# motor_control.net
KiCad netlist of a schematic drawn in EAGLE
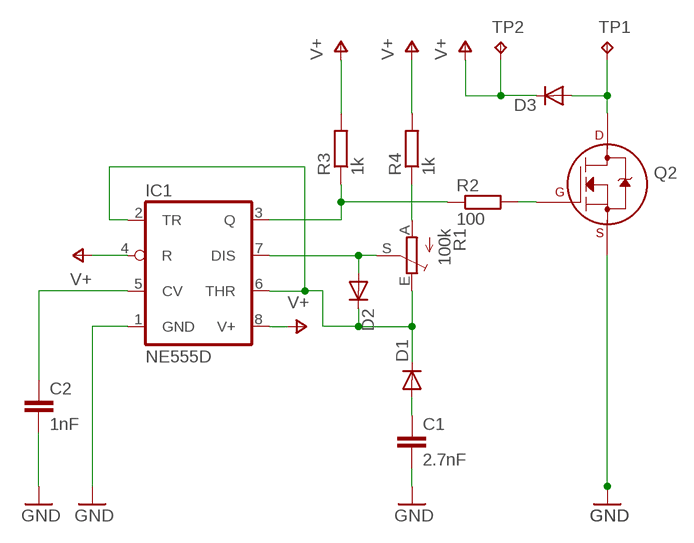
[diagram p0: schematic, sheet 1]

(export (version "E")
  (design (tool "Eeschema 10.0.6"))
  (components
    (comp (ref "C1")
      (value "2.7nF")
      (footprint "eagle-import:C0805")
      (libsource (lib "eagle-import") (part "C-EUC0805"))
    )
    (comp (ref "C2")
      (value "1nF")
      (footprint "eagle-import:C0805")
      (libsource (lib "eagle-import") (part "C-EUC0805"))
    )
    (comp (ref "D1")
      (value "DIODE-SMB")
      (footprint "eagle-import:SMB")
      (libsource (lib "eagle-import") (part "DIODE-SMB"))
    )
    (comp (ref "D2")
      (value "DIODE-SMB")
      (footprint "eagle-import:SMB")
      (libsource (lib "eagle-import") (part "DIODE-SMB"))
    )
    (comp (ref "D3")
      (value "DIODE-SMB")
      (footprint "eagle-import:SMB")
      (libsource (lib "eagle-import") (part "DIODE-SMB"))
    )
    (comp (ref "IC1")
      (value "NE555D")
      (footprint "eagle-import:SO08")
      (libsource (lib "eagle-import") (part "555DNE"))
    )
    (comp (ref "Q2")
      (value "2N7000_SOT23")
      (footprint "eagle-import:SOT-23")
      (libsource (lib "eagle-import") (part "2N700_SOT230"))
    )
    (comp (ref "R1")
      (value "100k")
      (footprint "eagle-import:CA6V")
      (libsource (lib "eagle-import") (part "TRIM_EU-CA6V"))
    )
    (comp (ref "R2")
      (value "100")
      (footprint "eagle-import:R0805")
      (libsource (lib "eagle-import") (part "R-EU_R0805"))
    )
    (comp (ref "R3")
      (value "1k")
      (footprint "eagle-import:R0805")
      (libsource (lib "eagle-import") (part "R-EU_R0805"))
    )
    (comp (ref "R4")
      (value "1k")
      (footprint "eagle-import:R0805")
      (libsource (lib "eagle-import") (part "R-EU_R0805"))
    )
    (comp (ref "TP1")
      (value "TPB2,54")
      (footprint "eagle-import:B2,54")
      (libsource (lib "eagle-import") (part "TPB2,54"))
    )
    (comp (ref "TP2")
      (value "TPB2,54")
      (footprint "eagle-import:B2,54")
      (libsource (lib "eagle-import") (part "TPB2,54"))
    )
  )
  (nets
    (net (code "1") (name "GND") (class "Default")
      (node (ref "C1") (pin "2") (pinfunction "2_2") (pintype "passive"))
      (node (ref "C2") (pin "2") (pinfunction "2_2") (pintype "passive"))
      (node (ref "IC1") (pin "1") (pinfunction "GND_1") (pintype "power_in"))
      (node (ref "Q2") (pin "2") (pinfunction "S_2") (pintype "bidirectional"))
    )
    (net (code "2") (name "Net-(C1-Pad1)") (class "Default")
      (node (ref "C1") (pin "1") (pinfunction "1_1") (pintype "passive"))
      (node (ref "D1") (pin "A") (pinfunction "A_A") (pintype "passive"))
    )
    (net (code "3") (name "Net-(IC1-CV)") (class "Default")
      (node (ref "C2") (pin "1") (pinfunction "1_1") (pintype "passive"))
      (node (ref "IC1") (pin "5") (pinfunction "CV_5") (pintype "input"))
    )
    (net (code "4") (name "Net-(IC1-DIS)") (class "Default")
      (node (ref "D2") (pin "A") (pinfunction "A_A") (pintype "passive"))
      (node (ref "IC1") (pin "7") (pinfunction "DIS_7") (pintype "input"))
      (node (ref "R1") (pin "S") (pinfunction "S_S") (pintype "passive"))
    )
    (net (code "5") (name "Net-(IC1-Q)") (class "Default")
      (node (ref "IC1") (pin "3") (pinfunction "Q_3") (pintype "output"))
      (node (ref "R2") (pin "1") (pinfunction "1_1") (pintype "passive"))
      (node (ref "R3") (pin "1") (pinfunction "1_1") (pintype "passive"))
    )
    (net (code "6") (name "Net-(IC1-THR)") (class "Default")
      (node (ref "D1") (pin "C") (pinfunction "C_C") (pintype "passive"))
      (node (ref "D2") (pin "C") (pinfunction "C_C") (pintype "passive"))
      (node (ref "IC1") (pin "2") (pinfunction "TR_2") (pintype "input"))
      (node (ref "IC1") (pin "6") (pinfunction "THR_6") (pintype "input"))
      (node (ref "R1") (pin "E") (pinfunction "E_E") (pintype "passive"))
    )
    (net (code "7") (name "Net-(Q2-D)") (class "Default")
      (node (ref "D3") (pin "A") (pinfunction "A_A") (pintype "passive"))
      (node (ref "Q2") (pin "3") (pinfunction "D_3") (pintype "bidirectional"))
      (node (ref "TP1") (pin "TP") (pinfunction "TP_TP") (pintype "input"))
    )
    (net (code "8") (name "Net-(Q2-G)") (class "Default")
      (node (ref "Q2") (pin "1") (pinfunction "G_1") (pintype "tri_state"))
      (node (ref "R2") (pin "2") (pinfunction "2_2") (pintype "passive"))
    )
    (net (code "9") (name "Net-(R1-PadA)") (class "Default")
      (node (ref "R1") (pin "A") (pinfunction "A_A") (pintype "passive"))
      (node (ref "R4") (pin "1") (pinfunction "1_1") (pintype "passive"))
    )
    (net (code "10") (name "V+") (class "Default")
      (node (ref "D3") (pin "C") (pinfunction "C_C") (pintype "passive"))
      (node (ref "IC1") (pin "4") (pinfunction "R_4") (pintype "input"))
      (node (ref "IC1") (pin "8") (pinfunction "V+_8") (pintype "power_in"))
      (node (ref "R3") (pin "2") (pinfunction "2_2") (pintype "passive"))
      (node (ref "R4") (pin "2") (pinfunction "2_2") (pintype "passive"))
      (node (ref "TP2") (pin "TP") (pinfunction "TP_TP") (pintype "input"))
    )
  )
)
